# Wireless.net
KiCad netlist of a schematic drawn in EAGLE
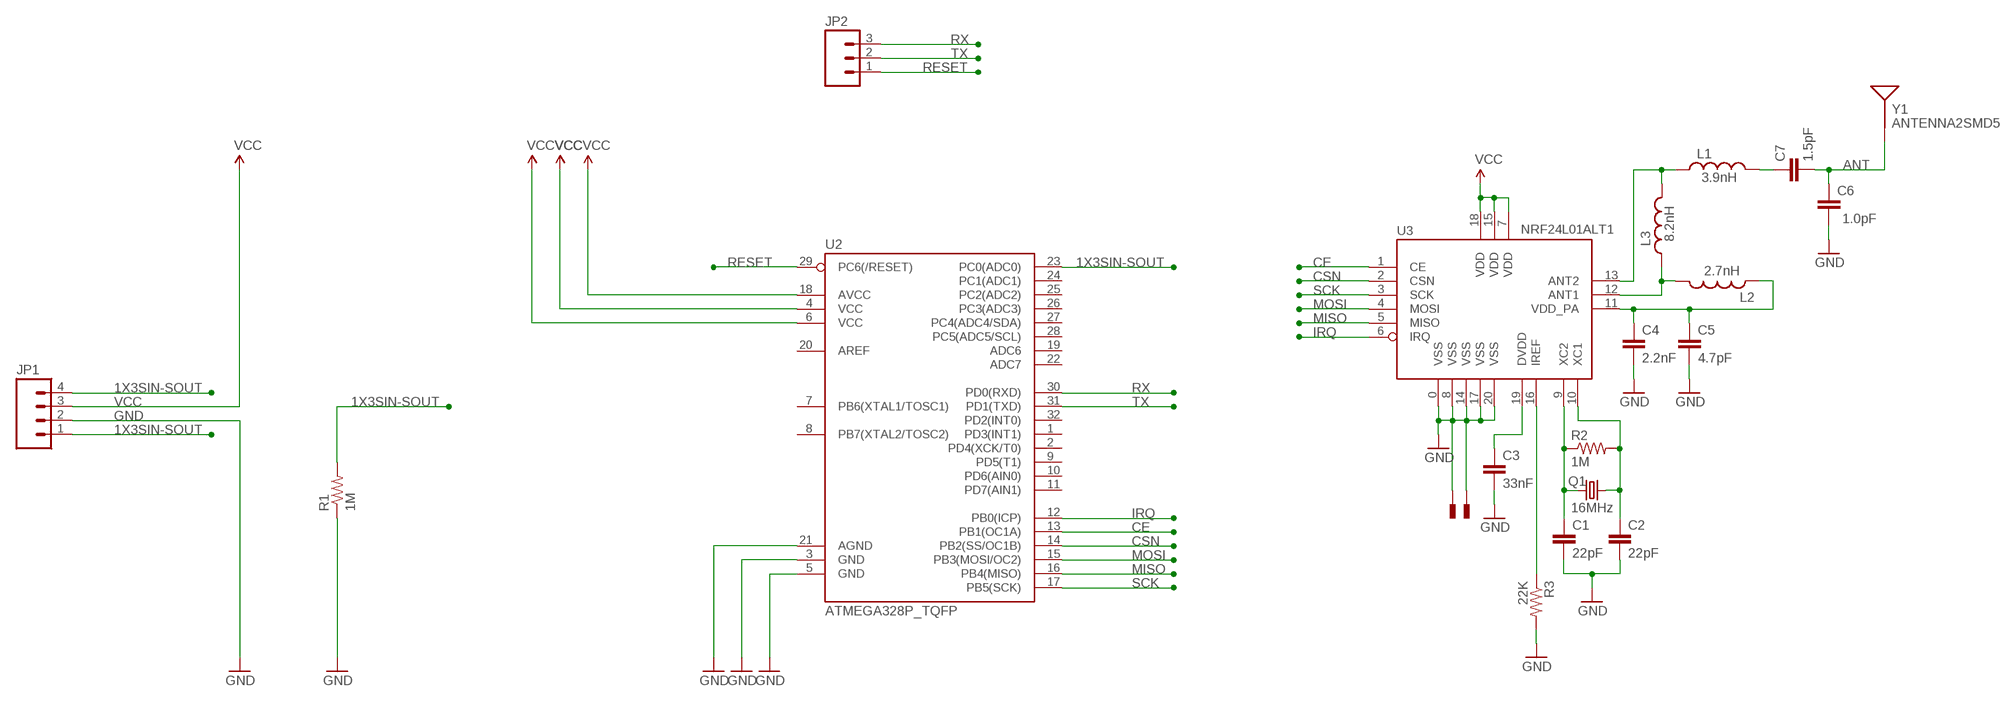
[diagram p0: schematic, sheet 1]

(export (version "E")
  (design (tool "Eeschema 10.0.6"))
  (components
    (comp (ref "C1")
      (value "22pF")
      (footprint "eagle-import:0402-CAP")
      (libsource (lib "eagle-import") (part "CAP0402-CAP"))
    )
    (comp (ref "C2")
      (value "22pF")
      (footprint "eagle-import:0402-CAP")
      (libsource (lib "eagle-import") (part "CAP0402-CAP"))
    )
    (comp (ref "C3")
      (value "33nF")
      (footprint "eagle-import:0402-CAP")
      (libsource (lib "eagle-import") (part "CAP0402-CAP"))
    )
    (comp (ref "C4")
      (value "2.2nF")
      (footprint "eagle-import:0402-CAP")
      (libsource (lib "eagle-import") (part "CAP0402-CAP"))
    )
    (comp (ref "C5")
      (value "4.7pF")
      (footprint "eagle-import:0402-CAP")
      (libsource (lib "eagle-import") (part "CAP0402-CAP"))
    )
    (comp (ref "C6")
      (value "1.0pF")
      (footprint "eagle-import:0402-CAP")
      (libsource (lib "eagle-import") (part "CAP0402-CAP"))
    )
    (comp (ref "C7")
      (value "1.5pF")
      (footprint "eagle-import:0402-CAP")
      (libsource (lib "eagle-import") (part "CAP0402-CAP"))
    )
    (comp (ref "JP1")
      (value "M04PTH")
      (footprint "eagle-import:1X04")
      (libsource (lib "eagle-import") (part "M04PTH"))
    )
    (comp (ref "JP2")
      (value "M03PTH")
      (footprint "eagle-import:1X03")
      (libsource (lib "eagle-import") (part "M03PTH"))
    )
    (comp (ref "L1")
      (value "3.9nH")
      (footprint "eagle-import:C0402")
      (libsource (lib "eagle-import") (part "INDUCTOR0402"))
    )
    (comp (ref "L2")
      (value "2.7nH")
      (footprint "eagle-import:C0402")
      (libsource (lib "eagle-import") (part "INDUCTOR0402"))
    )
    (comp (ref "L3")
      (value "8.2nH")
      (footprint "eagle-import:C0402")
      (libsource (lib "eagle-import") (part "INDUCTOR0402"))
    )
    (comp (ref "Q1")
      (value "16MHz")
      (footprint "eagle-import:CRYSTAL-SMD-5X3")
      (libsource (lib "eagle-import") (part "CRYSTAL5X3"))
    )
    (comp (ref "R1")
      (value "1M")
      (footprint "eagle-import:R0603")
      (libsource (lib "eagle-import") (part "R-US_R0603"))
    )
    (comp (ref "R2")
      (value "1M")
      (footprint "eagle-import:0402-RES")
      (libsource (lib "eagle-import") (part "RESISTOR0402-RES"))
    )
    (comp (ref "R3")
      (value "22K")
      (footprint "eagle-import:0402-RES")
      (libsource (lib "eagle-import") (part "RESISTOR0402-RES"))
    )
    (comp (ref "U$1")
      (value "PAD")
      (footprint "eagle-import:PAD-0.008")
      (libsource (lib "eagle-import") (part "PAD"))
    )
    (comp (ref "U$4")
      (value "PAD")
      (footprint "eagle-import:PAD-0.008")
      (libsource (lib "eagle-import") (part "PAD"))
    )
    (comp (ref "U2")
      (value "ATMEGA328P_TQFP")
      (footprint "eagle-import:TQFP32-08")
      (libsource (lib "eagle-import") (part "ATMEGA328P_TQFP"))
    )
    (comp (ref "U3")
      (value "NRF24L01ALT1")
      (footprint "eagle-import:QFN20_ALT1")
      (libsource (lib "eagle-import") (part "NRF24L01ALT1"))
    )
    (comp (ref "Y1")
      (value "ANTENNA2SMD5")
      (footprint "eagle-import:ANTENNA-CHIP5")
      (libsource (lib "eagle-import") (part "ANTENNA2SMD5"))
    )
  )
  (nets
    (net (code "1") (name "/1X3SIN-SOUT") (class "Default")
      (node (ref "JP1") (pin "1") (pinfunction "1_1") (pintype "passive"))
      (node (ref "JP1") (pin "4") (pinfunction "4_4") (pintype "passive"))
      (node (ref "R1") (pin "2") (pinfunction "2_2") (pintype "passive"))
      (node (ref "U2") (pin "23") (pinfunction "PC0(ADC0)_23") (pintype "bidirectional"))
    )
    (net (code "2") (name "/ANT") (class "Default")
      (node (ref "C6") (pin "2") (pinfunction "2_2") (pintype "passive"))
      (node (ref "C7") (pin "2") (pinfunction "2_2") (pintype "passive"))
      (node (ref "Y1") (pin "FEED") (pinfunction "SIGNAL_FEED") (pintype "bidirectional"))
    )
    (net (code "3") (name "/CE") (class "Default")
      (node (ref "U2") (pin "13") (pinfunction "PB1(OC1A)_13") (pintype "bidirectional"))
      (node (ref "U3") (pin "1") (pinfunction "CE_1") (pintype "input"))
    )
    (net (code "4") (name "/CSN") (class "Default")
      (node (ref "U2") (pin "14") (pinfunction "PB2(SS/OC1B)_14") (pintype "bidirectional"))
      (node (ref "U3") (pin "2") (pinfunction "CSN_2") (pintype "input"))
    )
    (net (code "5") (name "/IRQ") (class "Default")
      (node (ref "U2") (pin "12") (pinfunction "PB0(ICP)_12") (pintype "bidirectional"))
      (node (ref "U3") (pin "6") (pinfunction "IRQ_6") (pintype "output"))
    )
    (net (code "6") (name "/MISO") (class "Default")
      (node (ref "U2") (pin "16") (pinfunction "PB4(MISO)_16") (pintype "bidirectional"))
      (node (ref "U3") (pin "5") (pinfunction "MISO_5") (pintype "output"))
    )
    (net (code "7") (name "/MOSI") (class "Default")
      (node (ref "U2") (pin "15") (pinfunction "PB3(MOSI/OC2)_15") (pintype "bidirectional"))
      (node (ref "U3") (pin "4") (pinfunction "MOSI_4") (pintype "input"))
    )
    (net (code "8") (name "/RESET") (class "Default")
      (node (ref "JP2") (pin "1") (pinfunction "1_1") (pintype "passive"))
      (node (ref "U2") (pin "29") (pinfunction "PC6(/RESET)_29") (pintype "bidirectional"))
    )
    (net (code "9") (name "/RX") (class "Default")
      (node (ref "JP2") (pin "3") (pinfunction "3_3") (pintype "passive"))
      (node (ref "U2") (pin "30") (pinfunction "PD0(RXD)_30") (pintype "bidirectional"))
    )
    (net (code "10") (name "/SCK") (class "Default")
      (node (ref "U2") (pin "17") (pinfunction "PB5(SCK)_17") (pintype "bidirectional"))
      (node (ref "U3") (pin "3") (pinfunction "SCK_3") (pintype "input"))
    )
    (net (code "11") (name "/TX") (class "Default")
      (node (ref "JP2") (pin "2") (pinfunction "2_2") (pintype "passive"))
      (node (ref "U2") (pin "31") (pinfunction "PD1(TXD)_31") (pintype "bidirectional"))
    )
    (net (code "12") (name "GND") (class "Default")
      (node (ref "C1") (pin "2") (pinfunction "2_2") (pintype "passive"))
      (node (ref "C2") (pin "2") (pinfunction "2_2") (pintype "passive"))
      (node (ref "C3") (pin "2") (pinfunction "2_2") (pintype "passive"))
      (node (ref "C4") (pin "2") (pinfunction "2_2") (pintype "passive"))
      (node (ref "C5") (pin "2") (pinfunction "2_2") (pintype "passive"))
      (node (ref "C6") (pin "1") (pinfunction "1_1") (pintype "passive"))
      (node (ref "JP1") (pin "2") (pinfunction "2_2") (pintype "passive"))
      (node (ref "R1") (pin "1") (pinfunction "1_1") (pintype "passive"))
      (node (ref "R3") (pin "2") (pinfunction "2_2") (pintype "passive"))
      (node (ref "U$1") (pin "P$1") (pinfunction "P$1_P$1") (pintype "bidirectional"))
      (node (ref "U$4") (pin "P$1") (pinfunction "P$1_P$1") (pintype "bidirectional"))
      (node (ref "U2") (pin "21") (pinfunction "AGND_21") (pintype "bidirectional"))
      (node (ref "U2") (pin "3") (pinfunction "GND_3") (pintype "bidirectional"))
      (node (ref "U2") (pin "5") (pinfunction "GND_5") (pintype "bidirectional"))
      (node (ref "U3") (pin "0") (pinfunction "VSS_0") (pintype "power_in"))
      (node (ref "U3") (pin "14") (pinfunction "VSS_14") (pintype "power_in"))
      (node (ref "U3") (pin "17") (pinfunction "VSS_17") (pintype "power_in"))
      (node (ref "U3") (pin "20") (pinfunction "VSS_20") (pintype "power_in"))
      (node (ref "U3") (pin "8") (pinfunction "VSS_8") (pintype "power_in"))
    )
    (net (code "13") (name "Net-(C7-Pad1)") (class "Default")
      (node (ref "C7") (pin "1") (pinfunction "1_1") (pintype "passive"))
      (node (ref "L1") (pin "2") (pinfunction "2_2") (pintype "passive"))
    )
    (net (code "14") (name "Net-(Q1-2)") (class "Default")
      (node (ref "C2") (pin "1") (pinfunction "1_1") (pintype "passive"))
      (node (ref "Q1") (pin "3") (pinfunction "2_3") (pintype "passive"))
      (node (ref "R2") (pin "2") (pinfunction "2_2") (pintype "passive"))
      (node (ref "U3") (pin "10") (pinfunction "XC1_10") (pintype "input"))
    )
    (net (code "15") (name "Net-(U3-ANT1)") (class "Default")
      (node (ref "L2") (pin "2") (pinfunction "2_2") (pintype "passive"))
      (node (ref "L3") (pin "1") (pinfunction "1_1") (pintype "passive"))
      (node (ref "U3") (pin "12") (pinfunction "ANT1_12") (pintype "output"))
    )
    (net (code "16") (name "Net-(U3-ANT2)") (class "Default")
      (node (ref "L1") (pin "1") (pinfunction "1_1") (pintype "passive"))
      (node (ref "L3") (pin "2") (pinfunction "2_2") (pintype "passive"))
      (node (ref "U3") (pin "13") (pinfunction "ANT2_13") (pintype "output"))
    )
    (net (code "17") (name "Net-(U3-DVDD)") (class "Default")
      (node (ref "C3") (pin "1") (pinfunction "1_1") (pintype "passive"))
      (node (ref "U3") (pin "19") (pinfunction "DVDD_19") (pintype "power_in"))
    )
    (net (code "18") (name "Net-(U3-IREF)") (class "Default")
      (node (ref "R3") (pin "1") (pinfunction "1_1") (pintype "passive"))
      (node (ref "U3") (pin "16") (pinfunction "IREF_16") (pintype "input"))
    )
    (net (code "19") (name "Net-(U3-VDD_PA)") (class "Default")
      (node (ref "C4") (pin "1") (pinfunction "1_1") (pintype "passive"))
      (node (ref "C5") (pin "1") (pinfunction "1_1") (pintype "passive"))
      (node (ref "L2") (pin "1") (pinfunction "1_1") (pintype "passive"))
      (node (ref "U3") (pin "11") (pinfunction "VDD_PA_11") (pintype "power_in"))
    )
    (net (code "20") (name "Net-(U3-XC2)") (class "Default")
      (node (ref "C1") (pin "1") (pinfunction "1_1") (pintype "passive"))
      (node (ref "Q1") (pin "1") (pinfunction "1_1") (pintype "passive"))
      (node (ref "R2") (pin "1") (pinfunction "1_1") (pintype "passive"))
      (node (ref "U3") (pin "9") (pinfunction "XC2_9") (pintype "input"))
    )
    (net (code "21") (name "VCC") (class "Default")
      (node (ref "JP1") (pin "3") (pinfunction "3_3") (pintype "passive"))
      (node (ref "U2") (pin "18") (pinfunction "AVCC_18") (pintype "bidirectional"))
      (node (ref "U2") (pin "4") (pinfunction "VCC_4") (pintype "bidirectional"))
      (node (ref "U2") (pin "6") (pinfunction "VCC_6") (pintype "bidirectional"))
      (node (ref "U3") (pin "15") (pinfunction "VDD_15") (pintype "power_in"))
      (node (ref "U3") (pin "18") (pinfunction "VDD_18") (pintype "power_in"))
      (node (ref "U3") (pin "7") (pinfunction "VDD_7") (pintype "power_in"))
    )
    (net (code "22") (name "unconnected-(U2-ADC6-Pad19)") (class "Default")
      (node (ref "U2") (pin "19") (pinfunction "ADC6_19") (pintype "bidirectional"))
    )
    (net (code "23") (name "unconnected-(U2-ADC7-Pad22)") (class "Default")
      (node (ref "U2") (pin "22") (pinfunction "ADC7_22") (pintype "bidirectional"))
    )
    (net (code "24") (name "unconnected-(U2-AREF-Pad20)") (class "Default")
      (node (ref "U2") (pin "20") (pinfunction "AREF_20") (pintype "bidirectional"))
    )
    (net (code "25") (name "unconnected-(U2-PB6(XTAL1{slash}TOSC1)-Pad7)") (class "Default")
      (node (ref "U2") (pin "7") (pinfunction "PB6(XTAL1/TOSC1)_7") (pintype "bidirectional"))
    )
    (net (code "26") (name "unconnected-(U2-PB7(XTAL2{slash}TOSC2)-Pad8)") (class "Default")
      (node (ref "U2") (pin "8") (pinfunction "PB7(XTAL2/TOSC2)_8") (pintype "bidirectional"))
    )
    (net (code "27") (name "unconnected-(U2-PC1(ADC1)-Pad24)") (class "Default")
      (node (ref "U2") (pin "24") (pinfunction "PC1(ADC1)_24") (pintype "bidirectional"))
    )
    (net (code "28") (name "unconnected-(U2-PC2(ADC2)-Pad25)") (class "Default")
      (node (ref "U2") (pin "25") (pinfunction "PC2(ADC2)_25") (pintype "bidirectional"))
    )
    (net (code "29") (name "unconnected-(U2-PC3(ADC3)-Pad26)") (class "Default")
      (node (ref "U2") (pin "26") (pinfunction "PC3(ADC3)_26") (pintype "bidirectional"))
    )
    (net (code "30") (name "unconnected-(U2-PC4(ADC4{slash}SDA)-Pad27)") (class "Default")
      (node (ref "U2") (pin "27") (pinfunction "PC4(ADC4/SDA)_27") (pintype "bidirectional"))
    )
    (net (code "31") (name "unconnected-(U2-PC5(ADC5{slash}SCL)-Pad28)") (class "Default")
      (node (ref "U2") (pin "28") (pinfunction "PC5(ADC5/SCL)_28") (pintype "bidirectional"))
    )
    (net (code "32") (name "unconnected-(U2-PD2(INT0)-Pad32)") (class "Default")
      (node (ref "U2") (pin "32") (pinfunction "PD2(INT0)_32") (pintype "bidirectional"))
    )
    (net (code "33") (name "unconnected-(U2-PD3(INT1)-Pad1)") (class "Default")
      (node (ref "U2") (pin "1") (pinfunction "PD3(INT1)_1") (pintype "bidirectional"))
    )
    (net (code "34") (name "unconnected-(U2-PD4(XCK{slash}T0)-Pad2)") (class "Default")
      (node (ref "U2") (pin "2") (pinfunction "PD4(XCK/T0)_2") (pintype "bidirectional"))
    )
    (net (code "35") (name "unconnected-(U2-PD5(T1)-Pad9)") (class "Default")
      (node (ref "U2") (pin "9") (pinfunction "PD5(T1)_9") (pintype "bidirectional"))
    )
    (net (code "36") (name "unconnected-(U2-PD6(AIN0)-Pad10)") (class "Default")
      (node (ref "U2") (pin "10") (pinfunction "PD6(AIN0)_10") (pintype "bidirectional"))
    )
    (net (code "37") (name "unconnected-(U2-PD7(AIN1)-Pad11)") (class "Default")
      (node (ref "U2") (pin "11") (pinfunction "PD7(AIN1)_11") (pintype "bidirectional"))
    )
  )
)
